# tableau.net
KiCad netlist of a schematic drawn in EAGLE
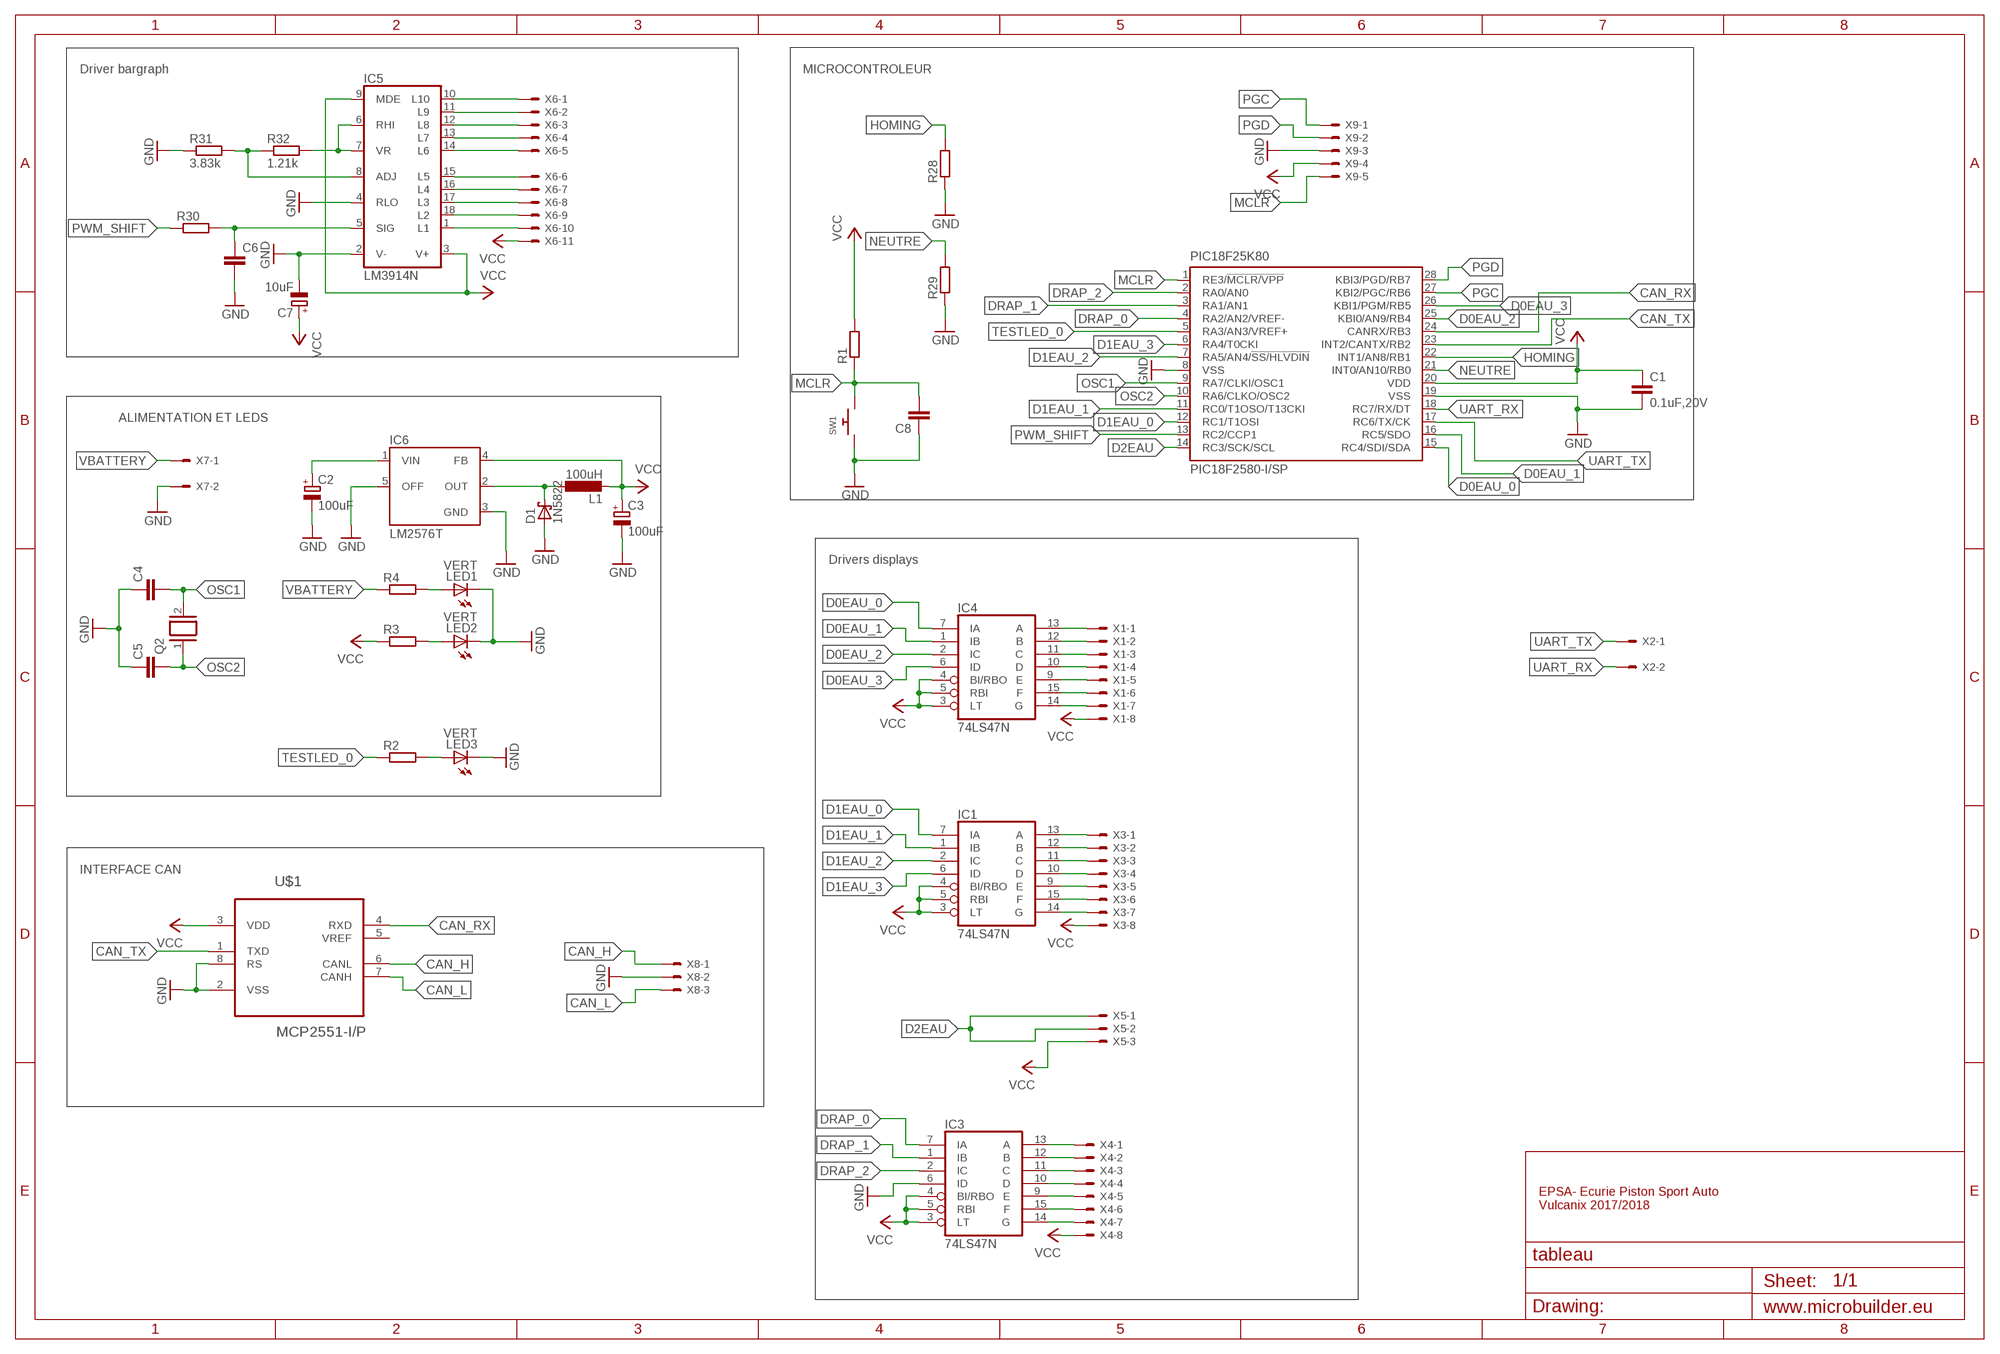
[diagram p0: schematic, sheet 1]

(export (version "E")
  (design (tool "Eeschema 10.0.6"))
  (components
    (comp (ref "C1")
      (value "0.1uF,20V")
      (footprint "eagle-import:C025-025X050")
      (libsource (lib "eagle-import") (part "C-EU025-025X050"))
    )
    (comp (ref "C2")
      (value "100uF")
      (footprint "eagle-import:E2-5")
      (libsource (lib "eagle-import") (part "CPOL-EUE2-5"))
    )
    (comp (ref "C3")
      (value "100uF")
      (footprint "eagle-import:E2-5")
      (libsource (lib "eagle-import") (part "CPOL-EUE2-5"))
    )
    (comp (ref "C4")
      (value "C-EU025-030X050")
      (footprint "eagle-import:C025-030X050")
      (libsource (lib "eagle-import") (part "C-EU025-030X050"))
    )
    (comp (ref "C5")
      (value "C-EU025-030X050")
      (footprint "eagle-import:C025-030X050")
      (libsource (lib "eagle-import") (part "C-EU025-030X050"))
    )
    (comp (ref "C6")
      (value "C-EU025-025X050")
      (footprint "eagle-import:C025-025X050")
      (libsource (lib "eagle-import") (part "resistor_C-EU025-025X050"))
    )
    (comp (ref "C7")
      (value "10uF")
      (footprint "eagle-import:E2-5")
      (libsource (lib "eagle-import") (part "CPOL-EUE2-5"))
    )
    (comp (ref "C8")
      (value "C-EU025-030X050")
      (footprint "eagle-import:C025-030X050")
      (libsource (lib "eagle-import") (part "C-EU025-030X050"))
    )
    (comp (ref "D1")
      (value "1N5822")
      (footprint "eagle-import:DO201T15")
      (libsource (lib "eagle-import") (part "SCHOTTKY-DIODEDO201T15"))
    )
    (comp (ref "IC1")
      (value "74LS47N")
      (footprint "eagle-import:DIL16")
      (libsource (lib "eagle-import") (part "7447NLS"))
    )
    (comp (ref "IC3")
      (value "74LS47N")
      (footprint "eagle-import:DIL16")
      (libsource (lib "eagle-import") (part "7447NLS"))
    )
    (comp (ref "IC4")
      (value "74LS47N")
      (footprint "eagle-import:DIL16")
      (libsource (lib "eagle-import") (part "7447NLS"))
    )
    (comp (ref "IC5")
      (value "LM3914N")
      (footprint "eagle-import:DIL18")
      (libsource (lib "eagle-import") (part "LM3914N"))
    )
    (comp (ref "IC6")
      (value "LM2576T")
      (footprint "eagle-import:TO220-5")
      (libsource (lib "eagle-import") (part "LM2576T"))
    )
    (comp (ref "L1")
      (value "100uH")
      (footprint "eagle-import:0207_10")
      (libsource (lib "eagle-import") (part "L-EU0207/10"))
    )
    (comp (ref "LED1")
      (value "VERT")
      (footprint "eagle-import:LED3MM")
      (libsource (lib "eagle-import") (part "LED3MM"))
    )
    (comp (ref "LED2")
      (value "VERT")
      (footprint "eagle-import:LED3MM")
      (libsource (lib "eagle-import") (part "LED3MM"))
    )
    (comp (ref "LED3")
      (value "VERT")
      (footprint "eagle-import:LED3MM")
      (libsource (lib "eagle-import") (part "LED3MM"))
    )
    (comp (ref "PIC18F25K80")
      (value "PIC18F2580-I/SP")
      (footprint "eagle-import:DIL28-3")
      (fields (field (name "MF") "MICROCHIP"))
      (libsource (lib "eagle-import") (part "PIC18F280-I/SP5"))
    )
    (comp (ref "Q2")
      (value "XTAL/S")
      (footprint "eagle-import:QS")
      (libsource (lib "eagle-import") (part "XTAL/S"))
    )
    (comp (ref "R1")
      (value "R-EU_0204/7")
      (footprint "eagle-import:0204_7")
      (libsource (lib "eagle-import") (part "R-EU_0204/7"))
    )
    (comp (ref "R2")
      (value "R-EU_0204/7")
      (footprint "eagle-import:0204_7")
      (libsource (lib "eagle-import") (part "R-EU_0204/7"))
    )
    (comp (ref "R3")
      (value "R-EU_0204/7")
      (footprint "eagle-import:0204_7")
      (libsource (lib "eagle-import") (part "R-EU_0204/7"))
    )
    (comp (ref "R4")
      (value "R-EU_0204/7")
      (footprint "eagle-import:0204_7")
      (libsource (lib "eagle-import") (part "R-EU_0204/7"))
    )
    (comp (ref "R28")
      (value "R-EU_0204/7")
      (footprint "eagle-import:0204_7")
      (libsource (lib "eagle-import") (part "R-EU_0204/7"))
    )
    (comp (ref "R29")
      (value "R-EU_0204/7")
      (footprint "eagle-import:0204_7")
      (libsource (lib "eagle-import") (part "R-EU_0204/7"))
    )
    (comp (ref "R30")
      (value "R-EU_0204/7")
      (footprint "eagle-import:0204_7")
      (libsource (lib "eagle-import") (part "R-EU_0204/7"))
    )
    (comp (ref "R31")
      (value "3.83k")
      (footprint "eagle-import:0204_7")
      (libsource (lib "eagle-import") (part "R-EU_0204/7"))
    )
    (comp (ref "R32")
      (value "1.21k")
      (footprint "eagle-import:0204_7")
      (libsource (lib "eagle-import") (part "R-EU_0204/7"))
    )
    (comp (ref "SW1")
      (value "SWITCH_PUSHBUTTONSOFTTOUCHSMD_SJ")
      (footprint "eagle-import:PUSHBUTTON_SMD_SJ")
      (libsource (lib "eagle-import") (part "SWITCH_PUSHBUTTONSOFTTOUCHSMD_SJ"))
    )
    (comp (ref "U$1")
      (value "MCP2551-I/P")
      (footprint "eagle-import:DIP254P762X432-8")
      (libsource (lib "eagle-import") (part "MCP2551-I/P"))
    )
    (comp (ref "X1")
      (value "KK-156-8")
      (footprint "eagle-import:KK-156-8")
      (libsource (lib "eagle-import") (part "KK-156-8"))
    )
    (comp (ref "X2")
      (value "KK-156-2")
      (footprint "eagle-import:KK-156-2")
      (libsource (lib "eagle-import") (part "KK-156-2"))
    )
    (comp (ref "X3")
      (value "KK-156-8")
      (footprint "eagle-import:KK-156-8")
      (libsource (lib "eagle-import") (part "KK-156-8"))
    )
    (comp (ref "X4")
      (value "KK-156-8")
      (footprint "eagle-import:KK-156-8")
      (libsource (lib "eagle-import") (part "KK-156-8"))
    )
    (comp (ref "X5")
      (value "KK-156-3")
      (footprint "eagle-import:KK-156-3")
      (libsource (lib "eagle-import") (part "KK-156-3"))
    )
    (comp (ref "X6")
      (value "KK-156-11")
      (footprint "eagle-import:KK-156-11")
      (libsource (lib "eagle-import") (part "KK-156-11"))
    )
    (comp (ref "X7")
      (value "KK-156-2")
      (footprint "eagle-import:KK-156-2")
      (libsource (lib "eagle-import") (part "KK-156-2"))
    )
    (comp (ref "X8")
      (value "KK-156-3")
      (footprint "eagle-import:KK-156-3")
      (libsource (lib "eagle-import") (part "KK-156-3"))
    )
    (comp (ref "X9")
      (value "KK-156-5")
      (footprint "eagle-import:KK-156-5")
      (libsource (lib "eagle-import") (part "KK-156-5"))
    )
  )
  (nets
    (net (code "1") (name "CAN_H") (class "Default")
      (node (ref "U$1") (pin "6") (pinfunction "CANL_6") (pintype "bidirectional"))
      (node (ref "X8") (pin "1") (pinfunction "S_1") (pintype "passive"))
    )
    (net (code "2") (name "CAN_L") (class "Default")
      (node (ref "U$1") (pin "7") (pinfunction "CANH_7") (pintype "bidirectional"))
      (node (ref "X8") (pin "3") (pinfunction "S_3") (pintype "passive"))
    )
    (net (code "3") (name "CAN_RX") (class "Default")
      (node (ref "PIC18F25K80") (pin "24") (pinfunction "CANRX/RB3_24") (pintype "bidirectional"))
      (node (ref "U$1") (pin "4") (pinfunction "RXD_4") (pintype "output"))
    )
    (net (code "4") (name "CAN_TX") (class "Default")
      (node (ref "PIC18F25K80") (pin "23") (pinfunction "INT2/CANTX/RB2_23") (pintype "bidirectional"))
      (node (ref "U$1") (pin "1") (pinfunction "TXD_1") (pintype "input"))
    )
    (net (code "5") (name "D0EAU_0") (class "Default")
      (node (ref "IC4") (pin "7") (pinfunction "IA_7") (pintype "input"))
      (node (ref "PIC18F25K80") (pin "15") (pinfunction "RC4/SDI/SDA_15") (pintype "bidirectional"))
    )
    (net (code "6") (name "D0EAU_1") (class "Default")
      (node (ref "IC4") (pin "1") (pinfunction "IB_1") (pintype "input"))
      (node (ref "PIC18F25K80") (pin "16") (pinfunction "RC5/SDO_16") (pintype "bidirectional"))
    )
    (net (code "7") (name "D0EAU_2") (class "Default")
      (node (ref "IC4") (pin "2") (pinfunction "IC_2") (pintype "input"))
      (node (ref "PIC18F25K80") (pin "25") (pinfunction "KBI0/AN9/RB4_25") (pintype "bidirectional"))
    )
    (net (code "8") (name "D0EAU_3") (class "Default")
      (node (ref "IC4") (pin "6") (pinfunction "ID_6") (pintype "input"))
      (node (ref "PIC18F25K80") (pin "26") (pinfunction "KBI1/PGM/RB5_26") (pintype "bidirectional"))
    )
    (net (code "9") (name "D1EAU_0") (class "Default")
      (node (ref "IC1") (pin "7") (pinfunction "IA_7") (pintype "input"))
      (node (ref "PIC18F25K80") (pin "12") (pinfunction "RC1/T1OSI_12") (pintype "bidirectional"))
    )
    (net (code "10") (name "D1EAU_1") (class "Default")
      (node (ref "IC1") (pin "1") (pinfunction "IB_1") (pintype "input"))
      (node (ref "PIC18F25K80") (pin "11") (pinfunction "RC0/T1OSO/T13CKI_11") (pintype "bidirectional"))
    )
    (net (code "11") (name "D1EAU_2") (class "Default")
      (node (ref "IC1") (pin "2") (pinfunction "IC_2") (pintype "input"))
      (node (ref "PIC18F25K80") (pin "7") (pinfunction "RA5/AN4/~{SS/HLVDIN}_7") (pintype "bidirectional"))
    )
    (net (code "12") (name "D1EAU_3") (class "Default")
      (node (ref "IC1") (pin "6") (pinfunction "ID_6") (pintype "input"))
      (node (ref "PIC18F25K80") (pin "6") (pinfunction "RA4/T0CKI_6") (pintype "bidirectional"))
    )
    (net (code "13") (name "D2EAU") (class "Default")
      (node (ref "PIC18F25K80") (pin "14") (pinfunction "RC3/SCK/SCL_14") (pintype "bidirectional"))
      (node (ref "X5") (pin "1") (pinfunction "S_1") (pintype "passive"))
      (node (ref "X5") (pin "2") (pinfunction "S_2") (pintype "passive"))
    )
    (net (code "14") (name "DRAP_0") (class "Default")
      (node (ref "IC3") (pin "7") (pinfunction "IA_7") (pintype "input"))
      (node (ref "PIC18F25K80") (pin "4") (pinfunction "RA2/AN2/VREF-_4") (pintype "bidirectional"))
    )
    (net (code "15") (name "DRAP_1") (class "Default")
      (node (ref "IC3") (pin "1") (pinfunction "IB_1") (pintype "input"))
      (node (ref "PIC18F25K80") (pin "3") (pinfunction "RA1/AN1_3") (pintype "bidirectional"))
    )
    (net (code "16") (name "DRAP_2") (class "Default")
      (node (ref "IC3") (pin "2") (pinfunction "IC_2") (pintype "input"))
      (node (ref "PIC18F25K80") (pin "2") (pinfunction "RA0/AN0_2") (pintype "bidirectional"))
    )
    (net (code "17") (name "GND") (class "Default")
      (node (ref "C1") (pin "2") (pinfunction "2_2") (pintype "passive"))
      (node (ref "C2") (pin "-") (pinfunction "-_-") (pintype "passive"))
      (node (ref "C3") (pin "-") (pinfunction "-_-") (pintype "passive"))
      (node (ref "C4") (pin "1") (pinfunction "1_1") (pintype "passive"))
      (node (ref "C5") (pin "1") (pinfunction "1_1") (pintype "passive"))
      (node (ref "C6") (pin "2") (pinfunction "2_2") (pintype "passive"))
      (node (ref "C7") (pin "-") (pinfunction "-_-") (pintype "passive"))
      (node (ref "C8") (pin "1") (pinfunction "1_1") (pintype "passive"))
      (node (ref "D1") (pin "A") (pinfunction "A_A") (pintype "passive"))
      (node (ref "IC3") (pin "6") (pinfunction "ID_6") (pintype "input"))
      (node (ref "IC5") (pin "2") (pinfunction "V-_2") (pintype "power_in"))
      (node (ref "IC5") (pin "4") (pinfunction "RLO_4") (pintype "input"))
      (node (ref "IC6") (pin "3") (pinfunction "GND_3") (pintype "power_in"))
      (node (ref "IC6") (pin "5") (pinfunction "OFF_5") (pintype "input"))
      (node (ref "LED1") (pin "K") (pinfunction "C_K") (pintype "passive"))
      (node (ref "LED2") (pin "K") (pinfunction "C_K") (pintype "passive"))
      (node (ref "LED3") (pin "K") (pinfunction "C_K") (pintype "passive"))
      (node (ref "PIC18F25K80") (pin "19") (pinfunction "VSS_19") (pintype "power_in"))
      (node (ref "PIC18F25K80") (pin "8") (pinfunction "VSS_8") (pintype "power_in"))
      (node (ref "R28") (pin "1") (pinfunction "1_1") (pintype "passive"))
      (node (ref "R29") (pin "1") (pinfunction "1_1") (pintype "passive"))
      (node (ref "R31") (pin "1") (pinfunction "1_1") (pintype "passive"))
      (node (ref "SW1") (pin "P$1") (pinfunction "P$1_P$1") (pintype "passive"))
      (node (ref "U$1") (pin "2") (pinfunction "VSS_2") (pintype "power_in"))
      (node (ref "U$1") (pin "8") (pinfunction "RS_8") (pintype "input"))
      (node (ref "X7") (pin "2") (pinfunction "S_2") (pintype "passive"))
      (node (ref "X8") (pin "2") (pinfunction "S_2") (pintype "passive"))
      (node (ref "X9") (pin "3") (pinfunction "S_3") (pintype "passive"))
    )
    (net (code "18") (name "HOMING") (class "Default")
      (node (ref "PIC18F25K80") (pin "22") (pinfunction "INT1/AN8/RB1_22") (pintype "bidirectional"))
      (node (ref "R28") (pin "2") (pinfunction "2_2") (pintype "passive"))
    )
    (net (code "19") (name "MCLR") (class "Default")
      (node (ref "C8") (pin "2") (pinfunction "2_2") (pintype "passive"))
      (node (ref "PIC18F25K80") (pin "1") (pinfunction "RE3/~{MCLR/VPP}_1") (pintype "input"))
      (node (ref "R1") (pin "1") (pinfunction "1_1") (pintype "passive"))
      (node (ref "SW1") (pin "P$2") (pinfunction "P$2_P$2") (pintype "passive"))
      (node (ref "X9") (pin "5") (pinfunction "S_5") (pintype "passive"))
    )
    (net (code "20") (name "NEUTRE") (class "Default")
      (node (ref "PIC18F25K80") (pin "21") (pinfunction "INT0/AN10/RB0_21") (pintype "bidirectional"))
      (node (ref "R29") (pin "2") (pinfunction "2_2") (pintype "passive"))
    )
    (net (code "21") (name "Net-(IC1A-A)") (class "Default")
      (node (ref "IC1") (pin "13") (pinfunction "A_13") (pintype "output"))
      (node (ref "X3") (pin "1") (pinfunction "S_1") (pintype "passive"))
    )
    (net (code "22") (name "Net-(IC1A-B)") (class "Default")
      (node (ref "IC1") (pin "12") (pinfunction "B_12") (pintype "output"))
      (node (ref "X3") (pin "2") (pinfunction "S_2") (pintype "passive"))
    )
    (net (code "23") (name "Net-(IC1A-C)") (class "Default")
      (node (ref "IC1") (pin "11") (pinfunction "C_11") (pintype "output"))
      (node (ref "X3") (pin "3") (pinfunction "S_3") (pintype "passive"))
    )
    (net (code "24") (name "Net-(IC1A-D)") (class "Default")
      (node (ref "IC1") (pin "10") (pinfunction "D_10") (pintype "output"))
      (node (ref "X3") (pin "4") (pinfunction "S_4") (pintype "passive"))
    )
    (net (code "25") (name "Net-(IC1A-E)") (class "Default")
      (node (ref "IC1") (pin "9") (pinfunction "E_9") (pintype "output"))
      (node (ref "X3") (pin "5") (pinfunction "S_5") (pintype "passive"))
    )
    (net (code "26") (name "Net-(IC1A-F)") (class "Default")
      (node (ref "IC1") (pin "15") (pinfunction "F_15") (pintype "output"))
      (node (ref "X3") (pin "6") (pinfunction "S_6") (pintype "passive"))
    )
    (net (code "27") (name "Net-(IC1A-G)") (class "Default")
      (node (ref "IC1") (pin "14") (pinfunction "G_14") (pintype "output"))
      (node (ref "X3") (pin "7") (pinfunction "S_7") (pintype "passive"))
    )
    (net (code "28") (name "Net-(IC3A-A)") (class "Default")
      (node (ref "IC3") (pin "13") (pinfunction "A_13") (pintype "output"))
      (node (ref "X4") (pin "1") (pinfunction "S_1") (pintype "passive"))
    )
    (net (code "29") (name "Net-(IC3A-B)") (class "Default")
      (node (ref "IC3") (pin "12") (pinfunction "B_12") (pintype "output"))
      (node (ref "X4") (pin "2") (pinfunction "S_2") (pintype "passive"))
    )
    (net (code "30") (name "Net-(IC3A-C)") (class "Default")
      (node (ref "IC3") (pin "11") (pinfunction "C_11") (pintype "output"))
      (node (ref "X4") (pin "3") (pinfunction "S_3") (pintype "passive"))
    )
    (net (code "31") (name "Net-(IC3A-D)") (class "Default")
      (node (ref "IC3") (pin "10") (pinfunction "D_10") (pintype "output"))
      (node (ref "X4") (pin "4") (pinfunction "S_4") (pintype "passive"))
    )
    (net (code "32") (name "Net-(IC3A-E)") (class "Default")
      (node (ref "IC3") (pin "9") (pinfunction "E_9") (pintype "output"))
      (node (ref "X4") (pin "5") (pinfunction "S_5") (pintype "passive"))
    )
    (net (code "33") (name "Net-(IC3A-F)") (class "Default")
      (node (ref "IC3") (pin "15") (pinfunction "F_15") (pintype "output"))
      (node (ref "X4") (pin "6") (pinfunction "S_6") (pintype "passive"))
    )
    (net (code "34") (name "Net-(IC3A-G)") (class "Default")
      (node (ref "IC3") (pin "14") (pinfunction "G_14") (pintype "output"))
      (node (ref "X4") (pin "7") (pinfunction "S_7") (pintype "passive"))
    )
    (net (code "35") (name "Net-(IC4A-A)") (class "Default")
      (node (ref "IC4") (pin "13") (pinfunction "A_13") (pintype "output"))
      (node (ref "X1") (pin "1") (pinfunction "S_1") (pintype "passive"))
    )
    (net (code "36") (name "Net-(IC4A-B)") (class "Default")
      (node (ref "IC4") (pin "12") (pinfunction "B_12") (pintype "output"))
      (node (ref "X1") (pin "2") (pinfunction "S_2") (pintype "passive"))
    )
    (net (code "37") (name "Net-(IC4A-C)") (class "Default")
      (node (ref "IC4") (pin "11") (pinfunction "C_11") (pintype "output"))
      (node (ref "X1") (pin "3") (pinfunction "S_3") (pintype "passive"))
    )
    (net (code "38") (name "Net-(IC4A-D)") (class "Default")
      (node (ref "IC4") (pin "10") (pinfunction "D_10") (pintype "output"))
      (node (ref "X1") (pin "4") (pinfunction "S_4") (pintype "passive"))
    )
    (net (code "39") (name "Net-(IC4A-E)") (class "Default")
      (node (ref "IC4") (pin "9") (pinfunction "E_9") (pintype "output"))
      (node (ref "X1") (pin "5") (pinfunction "S_5") (pintype "passive"))
    )
    (net (code "40") (name "Net-(IC4A-F)") (class "Default")
      (node (ref "IC4") (pin "15") (pinfunction "F_15") (pintype "output"))
      (node (ref "X1") (pin "6") (pinfunction "S_6") (pintype "passive"))
    )
    (net (code "41") (name "Net-(IC4A-G)") (class "Default")
      (node (ref "IC4") (pin "14") (pinfunction "G_14") (pintype "output"))
      (node (ref "X1") (pin "7") (pinfunction "S_7") (pintype "passive"))
    )
    (net (code "42") (name "Net-(IC5-ADJ)") (class "Default")
      (node (ref "IC5") (pin "8") (pinfunction "ADJ_8") (pintype "input"))
      (node (ref "R31") (pin "2") (pinfunction "2_2") (pintype "passive"))
      (node (ref "R32") (pin "1") (pinfunction "1_1") (pintype "passive"))
    )
    (net (code "43") (name "Net-(IC5-L1)") (class "Default")
      (node (ref "IC5") (pin "1") (pinfunction "L1_1") (pintype "output"))
      (node (ref "X6") (pin "10") (pinfunction "S_10") (pintype "passive"))
    )
    (net (code "44") (name "Net-(IC5-L2)") (class "Default")
      (node (ref "IC5") (pin "18") (pinfunction "L2_18") (pintype "output"))
      (node (ref "X6") (pin "9") (pinfunction "S_9") (pintype "passive"))
    )
    (net (code "45") (name "Net-(IC5-L3)") (class "Default")
      (node (ref "IC5") (pin "17") (pinfunction "L3_17") (pintype "output"))
      (node (ref "X6") (pin "8") (pinfunction "S_8") (pintype "passive"))
    )
    (net (code "46") (name "Net-(IC5-L4)") (class "Default")
      (node (ref "IC5") (pin "16") (pinfunction "L4_16") (pintype "output"))
      (node (ref "X6") (pin "7") (pinfunction "S_7") (pintype "passive"))
    )
    (net (code "47") (name "Net-(IC5-L5)") (class "Default")
      (node (ref "IC5") (pin "15") (pinfunction "L5_15") (pintype "output"))
      (node (ref "X6") (pin "6") (pinfunction "S_6") (pintype "passive"))
    )
    (net (code "48") (name "Net-(IC5-L6)") (class "Default")
      (node (ref "IC5") (pin "14") (pinfunction "L6_14") (pintype "output"))
      (node (ref "X6") (pin "5") (pinfunction "S_5") (pintype "passive"))
    )
    (net (code "49") (name "Net-(IC5-L7)") (class "Default")
      (node (ref "IC5") (pin "13") (pinfunction "L7_13") (pintype "output"))
      (node (ref "X6") (pin "4") (pinfunction "S_4") (pintype "passive"))
    )
    (net (code "50") (name "Net-(IC5-L8)") (class "Default")
      (node (ref "IC5") (pin "12") (pinfunction "L8_12") (pintype "output"))
      (node (ref "X6") (pin "3") (pinfunction "S_3") (pintype "passive"))
    )
    (net (code "51") (name "Net-(IC5-L9)") (class "Default")
      (node (ref "IC5") (pin "11") (pinfunction "L9_11") (pintype "output"))
      (node (ref "X6") (pin "2") (pinfunction "S_2") (pintype "passive"))
    )
    (net (code "52") (name "Net-(IC5-L10)") (class "Default")
      (node (ref "IC5") (pin "10") (pinfunction "L10_10") (pintype "output"))
      (node (ref "X6") (pin "1") (pinfunction "S_1") (pintype "passive"))
    )
    (net (code "53") (name "Net-(IC5-RHI)") (class "Default")
      (node (ref "IC5") (pin "6") (pinfunction "RHI_6") (pintype "input"))
      (node (ref "IC5") (pin "7") (pinfunction "VR_7") (pintype "output"))
      (node (ref "R32") (pin "2") (pinfunction "2_2") (pintype "passive"))
    )
    (net (code "54") (name "Net-(IC5-SIG)") (class "Default")
      (node (ref "C6") (pin "1") (pinfunction "1_1") (pintype "passive"))
      (node (ref "IC5") (pin "5") (pinfunction "SIG_5") (pintype "input"))
      (node (ref "R30") (pin "2") (pinfunction "2_2") (pintype "passive"))
    )
    (net (code "55") (name "Net-(IC6-OUT)") (class "Default")
      (node (ref "D1") (pin "C") (pinfunction "C_C") (pintype "passive"))
      (node (ref "IC6") (pin "2") (pinfunction "OUT_2") (pintype "output"))
      (node (ref "L1") (pin "1") (pinfunction "1_1") (pintype "passive"))
    )
    (net (code "56") (name "Net-(IC6-VIN)") (class "Default")
      (node (ref "C2") (pin "+") (pinfunction "+_+") (pintype "passive"))
      (node (ref "IC6") (pin "1") (pinfunction "VIN_1") (pintype "power_in"))
    )
    (net (code "57") (name "Net-(LED1-PadA)") (class "Default")
      (node (ref "LED1") (pin "A") (pinfunction "A_A") (pintype "passive"))
      (node (ref "R4") (pin "2") (pinfunction "2_2") (pintype "passive"))
    )
    (net (code "58") (name "Net-(LED2-PadA)") (class "Default")
      (node (ref "LED2") (pin "A") (pinfunction "A_A") (pintype "passive"))
      (node (ref "R3") (pin "2") (pinfunction "2_2") (pintype "passive"))
    )
    (net (code "59") (name "Net-(LED3-PadA)") (class "Default")
      (node (ref "LED3") (pin "A") (pinfunction "A_A") (pintype "passive"))
      (node (ref "R2") (pin "2") (pinfunction "2_2") (pintype "passive"))
    )
    (net (code "60") (name "OSC1") (class "Default")
      (node (ref "C4") (pin "2") (pinfunction "2_2") (pintype "passive"))
      (node (ref "PIC18F25K80") (pin "9") (pinfunction "RA7/CLKI/OSC1_9") (pintype "input"))
      (node (ref "Q2") (pin "2") (pinfunction "2_2") (pintype "passive"))
    )
    (net (code "61") (name "OSC2") (class "Default")
      (node (ref "C5") (pin "2") (pinfunction "2_2") (pintype "passive"))
      (node (ref "PIC18F25K80") (pin "10") (pinfunction "RA6/CLKO/OSC2_10") (pintype "output"))
      (node (ref "Q2") (pin "1") (pinfunction "1_1") (pintype "passive"))
    )
    (net (code "62") (name "PGC") (class "Default")
      (node (ref "PIC18F25K80") (pin "27") (pinfunction "KBI2/PGC/RB6_27") (pintype "bidirectional"))
      (node (ref "X9") (pin "1") (pinfunction "S_1") (pintype "passive"))
    )
    (net (code "63") (name "PGD") (class "Default")
      (node (ref "PIC18F25K80") (pin "28") (pinfunction "KBI3/PGD/RB7_28") (pintype "bidirectional"))
      (node (ref "X9") (pin "2") (pinfunction "S_2") (pintype "passive"))
    )
    (net (code "64") (name "PWM_SHIFT") (class "Default")
      (node (ref "PIC18F25K80") (pin "13") (pinfunction "RC2/CCP1_13") (pintype "bidirectional"))
      (node (ref "R30") (pin "1") (pinfunction "1_1") (pintype "passive"))
    )
    (net (code "65") (name "TESTLED_0") (class "Default")
      (node (ref "PIC18F25K80") (pin "5") (pinfunction "RA3/AN3/VREF+_5") (pintype "bidirectional"))
      (node (ref "R2") (pin "1") (pinfunction "1_1") (pintype "passive"))
    )
    (net (code "66") (name "UART_RX") (class "Default")
      (node (ref "PIC18F25K80") (pin "18") (pinfunction "RC7/RX/DT_18") (pintype "bidirectional"))
      (node (ref "X2") (pin "2") (pinfunction "S_2") (pintype "passive"))
    )
    (net (code "67") (name "UART_TX") (class "Default")
      (node (ref "PIC18F25K80") (pin "17") (pinfunction "RC6/TX/CK_17") (pintype "bidirectional"))
      (node (ref "X2") (pin "1") (pinfunction "S_1") (pintype "passive"))
    )
    (net (code "68") (name "VBATTERY") (class "Default")
      (node (ref "R4") (pin "1") (pinfunction "1_1") (pintype "passive"))
      (node (ref "X7") (pin "1") (pinfunction "S_1") (pintype "passive"))
    )
    (net (code "69") (name "VCC") (class "Default")
      (node (ref "C1") (pin "1") (pinfunction "1_1") (pintype "passive"))
      (node (ref "C3") (pin "+") (pinfunction "+_+") (pintype "passive"))
      (node (ref "C7") (pin "+") (pinfunction "+_+") (pintype "passive"))
      (node (ref "IC1") (pin "3") (pinfunction "LT_3") (pintype "input"))
      (node (ref "IC1") (pin "4") (pinfunction "BI/RBO_4") (pintype "input"))
      (node (ref "IC1") (pin "5") (pinfunction "RBI_5") (pintype "input"))
      (node (ref "IC3") (pin "3") (pinfunction "LT_3") (pintype "input"))
      (node (ref "IC3") (pin "4") (pinfunction "BI/RBO_4") (pintype "input"))
      (node (ref "IC3") (pin "5") (pinfunction "RBI_5") (pintype "input"))
      (node (ref "IC4") (pin "3") (pinfunction "LT_3") (pintype "input"))
      (node (ref "IC4") (pin "4") (pinfunction "BI/RBO_4") (pintype "input"))
      (node (ref "IC4") (pin "5") (pinfunction "RBI_5") (pintype "input"))
      (node (ref "IC5") (pin "3") (pinfunction "V+_3") (pintype "power_in"))
      (node (ref "IC5") (pin "9") (pinfunction "MDE_9") (pintype "input"))
      (node (ref "IC6") (pin "4") (pinfunction "FB_4") (pintype "input"))
      (node (ref "L1") (pin "2") (pinfunction "2_2") (pintype "passive"))
      (node (ref "PIC18F25K80") (pin "20") (pinfunction "VDD_20") (pintype "power_in"))
      (node (ref "R1") (pin "2") (pinfunction "2_2") (pintype "passive"))
      (node (ref "R3") (pin "1") (pinfunction "1_1") (pintype "passive"))
      (node (ref "U$1") (pin "3") (pinfunction "VDD_3") (pintype "power_in"))
      (node (ref "X1") (pin "8") (pinfunction "S_8") (pintype "passive"))
      (node (ref "X3") (pin "8") (pinfunction "S_8") (pintype "passive"))
      (node (ref "X4") (pin "8") (pinfunction "S_8") (pintype "passive"))
      (node (ref "X5") (pin "3") (pinfunction "S_3") (pintype "passive"))
      (node (ref "X6") (pin "11") (pinfunction "S_11") (pintype "passive"))
      (node (ref "X9") (pin "4") (pinfunction "S_4") (pintype "passive"))
    )
    (net (code "70") (name "unconnected-(U$1-VREF-Pad5)") (class "Default")
      (node (ref "U$1") (pin "5") (pinfunction "VREF_5") (pintype "output"))
    )
  )
)
